# esquema.net
KiCad netlist of a schematic drawn in EAGLE
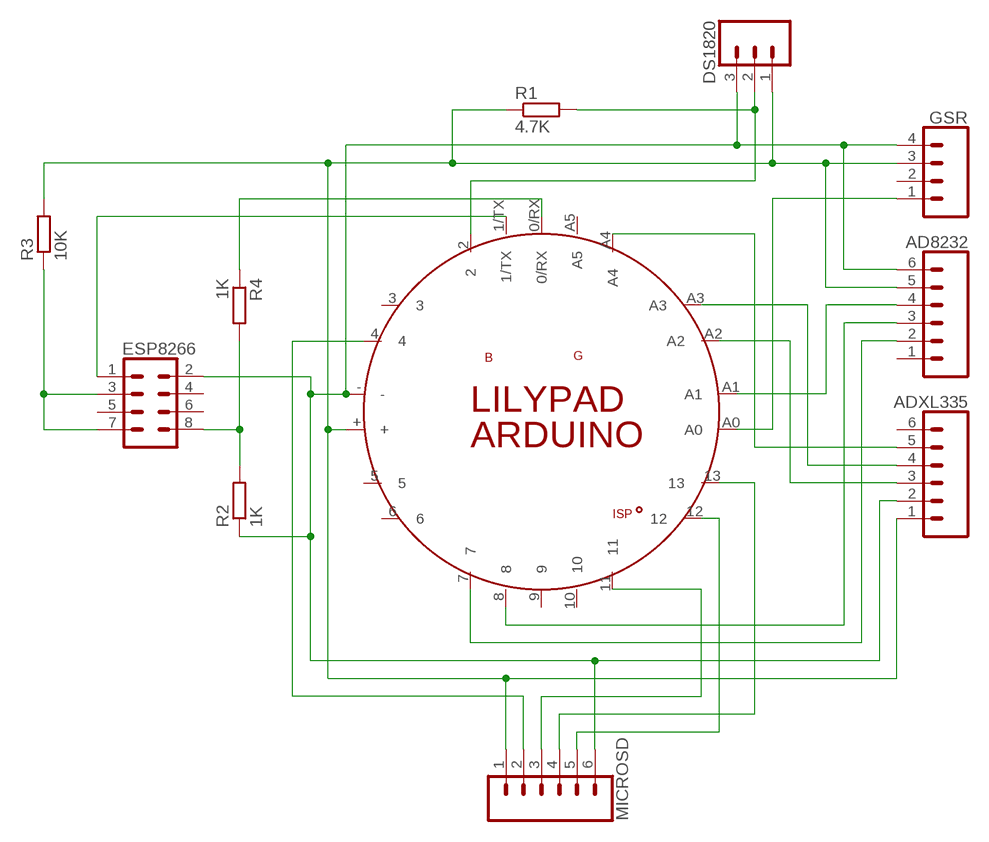
[diagram p0: schematic, sheet 1]

(export (version "E")
  (design (tool "Eeschema 10.0.6"))
  (components
    (comp (ref "AD8232")
      (value "CONN_06FEMALE_LOCK")
      (footprint "eagle-import:1X06_FEMALE_LOCK.010")
      (libsource (lib "eagle-import") (part "CONN_06FEMALE_LOCK"))
    )
    (comp (ref "ADXL335")
      (value "CONN_06FEMALE_LOCK")
      (footprint "eagle-import:1X06_FEMALE_LOCK.010")
      (libsource (lib "eagle-import") (part "CONN_06FEMALE_LOCK"))
    )
    (comp (ref "DS1820")
      (value "CONN_03")
      (footprint "eagle-import:1X03")
      (libsource (lib "eagle-import") (part "CONN_03"))
    )
    (comp (ref "ESP8266")
      (value "CONN_04X2")
      (footprint "eagle-import:2X4")
      (libsource (lib "eagle-import") (part "CONN_04X2"))
    )
    (comp (ref "GSR")
      (value "CONN_04JST-PTH")
      (footprint "eagle-import:JST-4-PTH")
      (libsource (lib "eagle-import") (part "CONN_04JST-PTH"))
    )
    (comp (ref "MICROSD")
      (value "CONN_06FEMALE_LOCK")
      (footprint "eagle-import:1X06_FEMALE_LOCK.010")
      (libsource (lib "eagle-import") (part "CONN_06FEMALE_LOCK"))
    )
    (comp (ref "PCB1")
      (value "ARDUINO_LILYPAD")
      (footprint "eagle-import:ARDUINO_LILYPAD")
      (libsource (lib "eagle-import") (part "ARDUINO_LILYPAD"))
    )
    (comp (ref "R1")
      (value "4.7K")
      (footprint "eagle-import:0309_12")
      (libsource (lib "eagle-import") (part "R-EU_0309/12"))
    )
    (comp (ref "R2")
      (value "1K")
      (footprint "eagle-import:0309_12")
      (libsource (lib "eagle-import") (part "R-EU_0309/12"))
    )
    (comp (ref "R3")
      (value "10K")
      (footprint "eagle-import:0309_12")
      (libsource (lib "eagle-import") (part "R-EU_0309/12"))
    )
    (comp (ref "R4")
      (value "1K")
      (footprint "eagle-import:0309_12")
      (libsource (lib "eagle-import") (part "R-EU_0309/12"))
    )
  )
  (nets
    (net (code "1") (name "Net-(AD8232-Pad2)") (class "Default")
      (node (ref "AD8232") (pin "2") (pinfunction "2_2") (pintype "passive"))
      (node (ref "PCB1") (pin "7") (pinfunction "7_7") (pintype "bidirectional"))
    )
    (net (code "2") (name "Net-(AD8232-Pad3)") (class "Default")
      (node (ref "AD8232") (pin "3") (pinfunction "3_3") (pintype "passive"))
      (node (ref "PCB1") (pin "8") (pinfunction "8_8") (pintype "bidirectional"))
    )
    (net (code "3") (name "Net-(AD8232-Pad4)") (class "Default")
      (node (ref "AD8232") (pin "4") (pinfunction "4_4") (pintype "passive"))
      (node (ref "PCB1") (pin "A1") (pinfunction "A1_A1") (pintype "bidirectional"))
    )
    (net (code "4") (name "Net-(AD8232-Pad5)") (class "Default")
      (node (ref "AD8232") (pin "5") (pinfunction "5_5") (pintype "passive"))
      (node (ref "ADXL335") (pin "1") (pinfunction "1_1") (pintype "passive"))
      (node (ref "DS1820") (pin "1") (pinfunction "1_1") (pintype "passive"))
      (node (ref "GSR") (pin "3") (pinfunction "3_3") (pintype "passive"))
      (node (ref "MICROSD") (pin "1") (pinfunction "1_1") (pintype "passive"))
      (node (ref "PCB1") (pin "+") (pinfunction "+_+") (pintype "bidirectional"))
      (node (ref "R1") (pin "1") (pinfunction "1_1") (pintype "passive"))
      (node (ref "R3") (pin "2") (pinfunction "2_2") (pintype "passive"))
    )
    (net (code "5") (name "Net-(AD8232-Pad6)") (class "Default")
      (node (ref "AD8232") (pin "6") (pinfunction "6_6") (pintype "passive"))
      (node (ref "ADXL335") (pin "2") (pinfunction "2_2") (pintype "passive"))
      (node (ref "DS1820") (pin "3") (pinfunction "3_3") (pintype "passive"))
      (node (ref "ESP8266") (pin "2") (pinfunction "2_2") (pintype "passive"))
      (node (ref "GSR") (pin "4") (pinfunction "4_4") (pintype "passive"))
      (node (ref "MICROSD") (pin "6") (pinfunction "6_6") (pintype "passive"))
      (node (ref "PCB1") (pin "-") (pinfunction "-_-") (pintype "bidirectional"))
      (node (ref "R2") (pin "1") (pinfunction "1_1") (pintype "passive"))
    )
    (net (code "6") (name "Net-(ADXL335-Pad3)") (class "Default")
      (node (ref "ADXL335") (pin "3") (pinfunction "3_3") (pintype "passive"))
      (node (ref "PCB1") (pin "A2") (pinfunction "A2_A2") (pintype "bidirectional"))
    )
    (net (code "7") (name "Net-(ADXL335-Pad4)") (class "Default")
      (node (ref "ADXL335") (pin "4") (pinfunction "4_4") (pintype "passive"))
      (node (ref "PCB1") (pin "A3") (pinfunction "A3_A3") (pintype "bidirectional"))
    )
    (net (code "8") (name "Net-(ADXL335-Pad5)") (class "Default")
      (node (ref "ADXL335") (pin "5") (pinfunction "5_5") (pintype "passive"))
      (node (ref "PCB1") (pin "A4") (pinfunction "A4_A4") (pintype "bidirectional"))
    )
    (net (code "9") (name "Net-(DS1820-Pad2)") (class "Default")
      (node (ref "DS1820") (pin "2") (pinfunction "2_2") (pintype "passive"))
      (node (ref "PCB1") (pin "2") (pinfunction "2_2") (pintype "bidirectional"))
      (node (ref "R1") (pin "2") (pinfunction "2_2") (pintype "passive"))
    )
    (net (code "10") (name "Net-(ESP8266-Pad1)") (class "Default")
      (node (ref "ESP8266") (pin "1") (pinfunction "1_1") (pintype "passive"))
      (node (ref "PCB1") (pin "1/TX") (pinfunction "1/TX_1/TX") (pintype "bidirectional"))
    )
    (net (code "11") (name "Net-(ESP8266-Pad3)") (class "Default")
      (node (ref "ESP8266") (pin "3") (pinfunction "3_3") (pintype "passive"))
      (node (ref "ESP8266") (pin "7") (pinfunction "7_7") (pintype "passive"))
      (node (ref "R3") (pin "1") (pinfunction "1_1") (pintype "passive"))
    )
    (net (code "12") (name "Net-(ESP8266-Pad8)") (class "Default")
      (node (ref "ESP8266") (pin "8") (pinfunction "8_8") (pintype "passive"))
      (node (ref "R2") (pin "2") (pinfunction "2_2") (pintype "passive"))
      (node (ref "R4") (pin "2") (pinfunction "2_2") (pintype "passive"))
    )
    (net (code "13") (name "Net-(GSR-Pad1)") (class "Default")
      (node (ref "GSR") (pin "1") (pinfunction "1_1") (pintype "passive"))
      (node (ref "PCB1") (pin "A0") (pinfunction "A0_A0") (pintype "bidirectional"))
    )
    (net (code "14") (name "Net-(MICROSD-Pad2)") (class "Default")
      (node (ref "MICROSD") (pin "2") (pinfunction "2_2") (pintype "passive"))
      (node (ref "PCB1") (pin "4") (pinfunction "4_4") (pintype "bidirectional"))
    )
    (net (code "15") (name "Net-(MICROSD-Pad3)") (class "Default")
      (node (ref "MICROSD") (pin "3") (pinfunction "3_3") (pintype "passive"))
      (node (ref "PCB1") (pin "11") (pinfunction "11_11") (pintype "bidirectional"))
    )
    (net (code "16") (name "Net-(MICROSD-Pad4)") (class "Default")
      (node (ref "MICROSD") (pin "4") (pinfunction "4_4") (pintype "passive"))
      (node (ref "PCB1") (pin "13") (pinfunction "13_13") (pintype "bidirectional"))
    )
    (net (code "17") (name "Net-(MICROSD-Pad5)") (class "Default")
      (node (ref "MICROSD") (pin "5") (pinfunction "5_5") (pintype "passive"))
      (node (ref "PCB1") (pin "12") (pinfunction "12_12") (pintype "bidirectional"))
    )
    (net (code "18") (name "Net-(PCB1-Pad0{slash}RX)") (class "Default")
      (node (ref "PCB1") (pin "0/RX") (pinfunction "0/RX_0/RX") (pintype "bidirectional"))
      (node (ref "R4") (pin "1") (pinfunction "1_1") (pintype "passive"))
    )
    (net (code "19") (name "unconnected-(AD8232-Pad1)") (class "Default")
      (node (ref "AD8232") (pin "1") (pinfunction "1_1") (pintype "passive"))
    )
    (net (code "20") (name "unconnected-(ADXL335-Pad6)") (class "Default")
      (node (ref "ADXL335") (pin "6") (pinfunction "6_6") (pintype "passive"))
    )
    (net (code "21") (name "unconnected-(ESP8266-Pad4)") (class "Default")
      (node (ref "ESP8266") (pin "4") (pinfunction "4_4") (pintype "passive"))
    )
    (net (code "22") (name "unconnected-(ESP8266-Pad5)") (class "Default")
      (node (ref "ESP8266") (pin "5") (pinfunction "5_5") (pintype "passive"))
    )
    (net (code "23") (name "unconnected-(ESP8266-Pad6)") (class "Default")
      (node (ref "ESP8266") (pin "6") (pinfunction "6_6") (pintype "passive"))
    )
    (net (code "24") (name "unconnected-(GSR-Pad2)") (class "Default")
      (node (ref "GSR") (pin "2") (pinfunction "2_2") (pintype "passive"))
    )
    (net (code "25") (name "unconnected-(PCB1-GND-PadGND_)") (class "Default")
      (node (ref "PCB1") (pin "GND_") (pinfunction "GND_GND_") (pintype "bidirectional"))
    )
    (net (code "26") (name "unconnected-(PCB1-Pad3)") (class "Default")
      (node (ref "PCB1") (pin "3") (pinfunction "3_3") (pintype "bidirectional"))
    )
    (net (code "27") (name "unconnected-(PCB1-Pad5)") (class "Default")
      (node (ref "PCB1") (pin "5") (pinfunction "5_5") (pintype "bidirectional"))
    )
    (net (code "28") (name "unconnected-(PCB1-Pad6)") (class "Default")
      (node (ref "PCB1") (pin "6") (pinfunction "6_6") (pintype "bidirectional"))
    )
    (net (code "29") (name "unconnected-(PCB1-Pad9)") (class "Default")
      (node (ref "PCB1") (pin "9") (pinfunction "9_9") (pintype "bidirectional"))
    )
    (net (code "30") (name "unconnected-(PCB1-Pad10)") (class "Default")
      (node (ref "PCB1") (pin "10") (pinfunction "10_10") (pintype "bidirectional"))
    )
    (net (code "31") (name "unconnected-(PCB1-PadA5)") (class "Default")
      (node (ref "PCB1") (pin "A5") (pinfunction "A5_A5") (pintype "bidirectional"))
    )
    (net (code "32") (name "unconnected-(PCB1-PadDTR)") (class "Default")
      (node (ref "PCB1") (pin "DTR") (pinfunction "DTR_DTR") (pintype "bidirectional"))
    )
    (net (code "33") (name "unconnected-(PCB1-PadGND.)") (class "Default")
      (node (ref "PCB1") (pin "GND.") (pinfunction "GND._GND.") (pintype "bidirectional"))
    )
    (net (code "34") (name "unconnected-(PCB1-PadGND..)") (class "Default")
      (node (ref "PCB1") (pin "GND..") (pinfunction "GND.._GND..") (pintype "bidirectional"))
    )
    (net (code "35") (name "unconnected-(PCB1-PadMISO)") (class "Default")
      (node (ref "PCB1") (pin "MISO") (pinfunction "MISO_MISO") (pintype "bidirectional"))
    )
    (net (code "36") (name "unconnected-(PCB1-PadMOSI)") (class "Default")
      (node (ref "PCB1") (pin "MOSI") (pinfunction "MOSI_MOSI") (pintype "bidirectional"))
    )
    (net (code "37") (name "unconnected-(PCB1-PadRXI)") (class "Default")
      (node (ref "PCB1") (pin "RXI") (pinfunction "RXI_RXI") (pintype "bidirectional"))
    )
    (net (code "38") (name "unconnected-(PCB1-PadSCK)") (class "Default")
      (node (ref "PCB1") (pin "SCK") (pinfunction "SCK_SCK") (pintype "bidirectional"))
    )
    (net (code "39") (name "unconnected-(PCB1-PadTXO)") (class "Default")
      (node (ref "PCB1") (pin "TXO") (pinfunction "TXO_TXO") (pintype "bidirectional"))
    )
    (net (code "40") (name "unconnected-(PCB1-PadVCC.)") (class "Default")
      (node (ref "PCB1") (pin "VCC.") (pinfunction "VCC._VCC.") (pintype "bidirectional"))
    )
    (net (code "41") (name "unconnected-(PCB1-RST-PadRESET..)") (class "Default")
      (node (ref "PCB1") (pin "RESET..") (pinfunction "RST_RESET..") (pintype "bidirectional"))
    )
    (net (code "42") (name "unconnected-(PCB1-VCC-Pad5V.)") (class "Default")
      (node (ref "PCB1") (pin "5V.") (pinfunction "VCC_5V.") (pintype "bidirectional"))
    )
  )
)
